# Filtering_stages.net
KiCad netlist of a schematic drawn in EAGLE
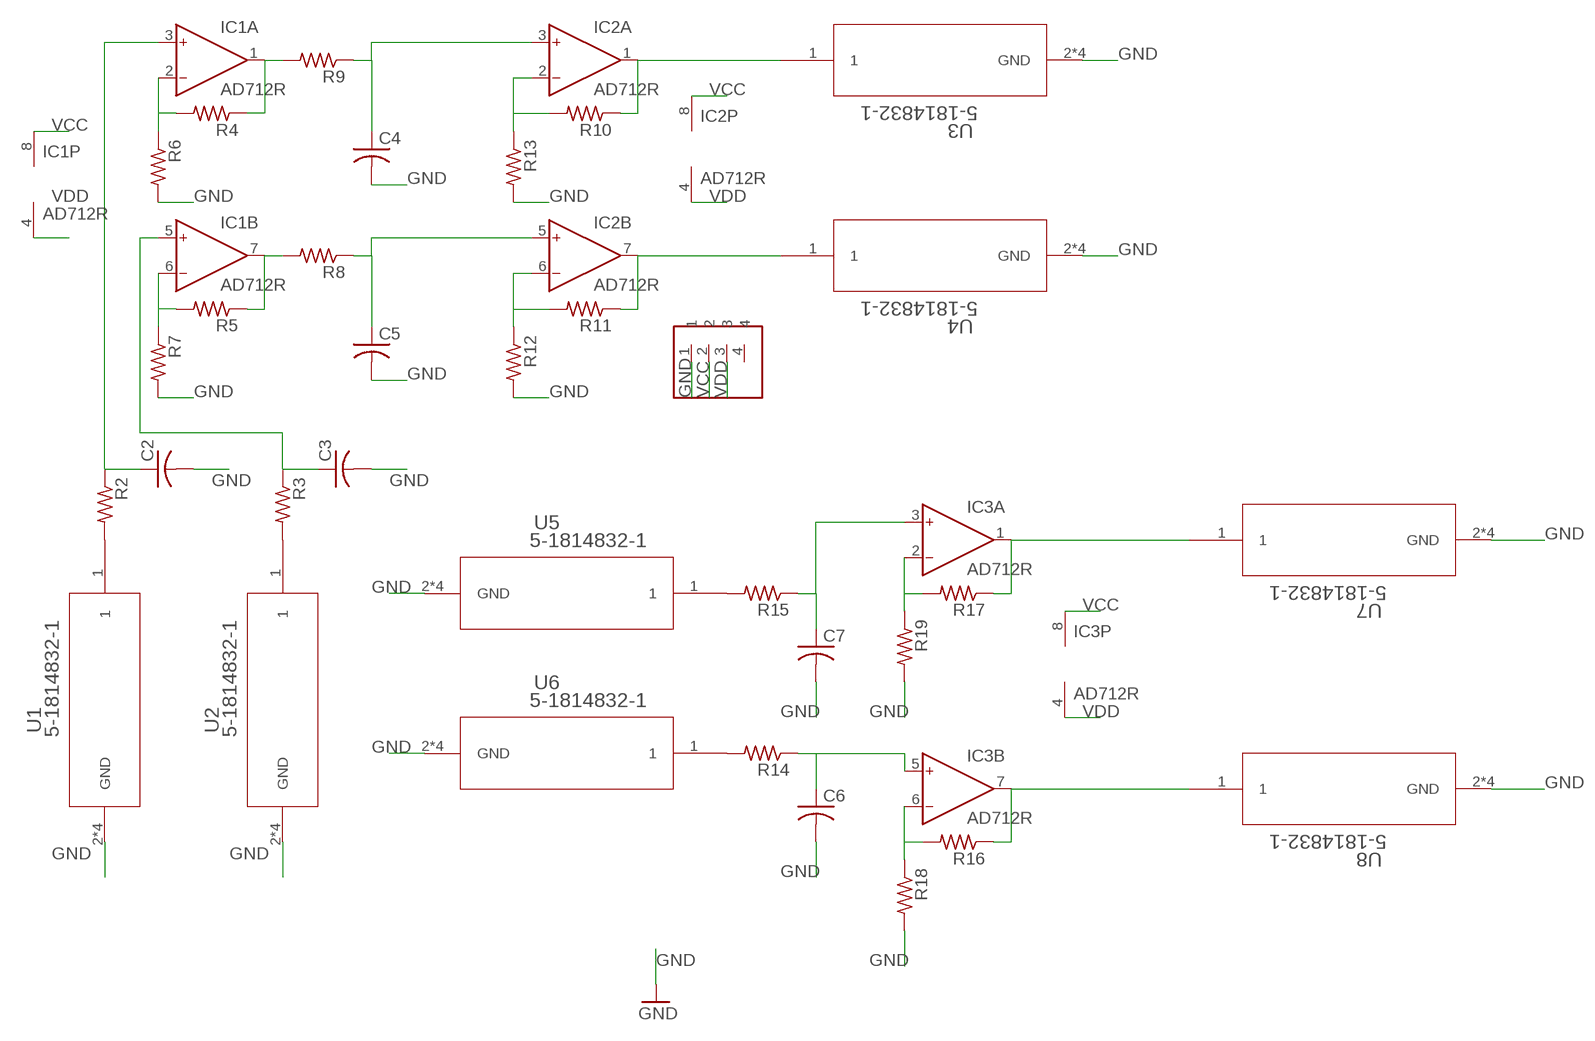
[diagram p0: schematic, sheet 1]

(export (version "E")
  (design (tool "Eeschema 10.0.6"))
  (components
    (comp (ref "C2")
      (value "C-US025-025X050")
      (footprint "eagle-import:C025-025X050")
      (libsource (lib "eagle-import") (part "C-US025-025X050"))
    )
    (comp (ref "C3")
      (value "C-US025-025X050")
      (footprint "eagle-import:C025-025X050")
      (libsource (lib "eagle-import") (part "C-US025-025X050"))
    )
    (comp (ref "C4")
      (value "C-US025-025X050")
      (footprint "eagle-import:C025-025X050")
      (libsource (lib "eagle-import") (part "C-US025-025X050"))
    )
    (comp (ref "C5")
      (value "C-US025-025X050")
      (footprint "eagle-import:C025-025X050")
      (libsource (lib "eagle-import") (part "C-US025-025X050"))
    )
    (comp (ref "C6")
      (value "C-US025-025X050")
      (footprint "eagle-import:C025-025X050")
      (libsource (lib "eagle-import") (part "C-US025-025X050"))
    )
    (comp (ref "C7")
      (value "C-US025-025X050")
      (footprint "eagle-import:C025-025X050")
      (libsource (lib "eagle-import") (part "C-US025-025X050"))
    )
    (comp (ref "IC1")
      (value "AD712R")
      (footprint "eagle-import:SO8")
      (fields (field (name "MF") "ALTERA CORPORATION") (field (name "MPN") "AD712KRZ"))
      (libsource (lib "eagle-import") (part "AD712R"))
    )
    (comp (ref "IC2")
      (value "AD712R")
      (footprint "eagle-import:SO8")
      (fields (field (name "MF") "ALTERA CORPORATION") (field (name "MPN") "AD712KRZ"))
      (libsource (lib "eagle-import") (part "AD712R"))
    )
    (comp (ref "IC3")
      (value "AD712R")
      (footprint "eagle-import:SO8")
      (fields (field (name "MF") "ALTERA CORPORATION") (field (name "MPN") "AD712KRZ"))
      (libsource (lib "eagle-import") (part "AD712R"))
    )
    (comp (ref "R2")
      (value "R-US_0204/7")
      (footprint "eagle-import:0204_7")
      (libsource (lib "eagle-import") (part "R-US_0204/7"))
    )
    (comp (ref "R3")
      (value "R-US_0204/7")
      (footprint "eagle-import:0204_7")
      (libsource (lib "eagle-import") (part "R-US_0204/7"))
    )
    (comp (ref "R4")
      (value "R-US_0204/7")
      (footprint "eagle-import:0204_7")
      (libsource (lib "eagle-import") (part "R-US_0204/7"))
    )
    (comp (ref "R5")
      (value "R-US_0204/7")
      (footprint "eagle-import:0204_7")
      (libsource (lib "eagle-import") (part "R-US_0204/7"))
    )
    (comp (ref "R6")
      (value "R-US_0204/7")
      (footprint "eagle-import:0204_7")
      (libsource (lib "eagle-import") (part "R-US_0204/7"))
    )
    (comp (ref "R7")
      (value "R-US_0204/7")
      (footprint "eagle-import:0204_7")
      (libsource (lib "eagle-import") (part "R-US_0204/7"))
    )
    (comp (ref "R8")
      (value "R-US_0204/7")
      (footprint "eagle-import:0204_7")
      (libsource (lib "eagle-import") (part "R-US_0204/7"))
    )
    (comp (ref "R9")
      (value "R-US_0204/7")
      (footprint "eagle-import:0204_7")
      (libsource (lib "eagle-import") (part "R-US_0204/7"))
    )
    (comp (ref "R10")
      (value "R-US_0204/7")
      (footprint "eagle-import:0204_7")
      (libsource (lib "eagle-import") (part "R-US_0204/7"))
    )
    (comp (ref "R11")
      (value "R-US_0204/7")
      (footprint "eagle-import:0204_7")
      (libsource (lib "eagle-import") (part "R-US_0204/7"))
    )
    (comp (ref "R12")
      (value "R-US_0204/7")
      (footprint "eagle-import:0204_7")
      (libsource (lib "eagle-import") (part "R-US_0204/7"))
    )
    (comp (ref "R13")
      (value "R-US_0204/7")
      (footprint "eagle-import:0204_7")
      (libsource (lib "eagle-import") (part "R-US_0204/7"))
    )
    (comp (ref "R14")
      (value "R-US_0204/7")
      (footprint "eagle-import:0204_7")
      (libsource (lib "eagle-import") (part "R-US_0204/7"))
    )
    (comp (ref "R15")
      (value "R-US_0204/7")
      (footprint "eagle-import:0204_7")
      (libsource (lib "eagle-import") (part "R-US_0204/7"))
    )
    (comp (ref "R16")
      (value "R-US_0204/7")
      (footprint "eagle-import:0204_7")
      (libsource (lib "eagle-import") (part "R-US_0204/7"))
    )
    (comp (ref "R17")
      (value "R-US_0204/7")
      (footprint "eagle-import:0204_7")
      (libsource (lib "eagle-import") (part "R-US_0204/7"))
    )
    (comp (ref "R18")
      (value "R-US_0204/7")
      (footprint "eagle-import:0204_7")
      (libsource (lib "eagle-import") (part "R-US_0204/7"))
    )
    (comp (ref "R19")
      (value "R-US_0204/7")
      (footprint "eagle-import:0204_7")
      (libsource (lib "eagle-import") (part "R-US_0204/7"))
    )
    (comp (ref "U$1")
      (value "ED2582-ND")
      (footprint "eagle-import:ED2582-ND")
      (libsource (lib "eagle-import") (part "ED2582-ND"))
    )
    (comp (ref "U1")
      (value "5-1814832-1")
      (footprint "eagle-import:5-1814832-1")
      (fields (field (name "COPYRIGHT") "Copyright (C) 2015 Accelerated Designs. All rights reserved"))
      (libsource (lib "eagle-import") (part "5-1814832-1"))
    )
    (comp (ref "U2")
      (value "5-1814832-1")
      (footprint "eagle-import:5-1814832-1")
      (fields (field (name "COPYRIGHT") "Copyright (C) 2015 Accelerated Designs. All rights reserved"))
      (libsource (lib "eagle-import") (part "5-1814832-1"))
    )
    (comp (ref "U3")
      (value "5-1814832-1")
      (footprint "eagle-import:5-1814832-1")
      (fields (field (name "COPYRIGHT") "Copyright (C) 2015 Accelerated Designs. All rights reserved"))
      (libsource (lib "eagle-import") (part "5-1814832-1"))
    )
    (comp (ref "U4")
      (value "5-1814832-1")
      (footprint "eagle-import:5-1814832-1")
      (fields (field (name "COPYRIGHT") "Copyright (C) 2015 Accelerated Designs. All rights reserved"))
      (libsource (lib "eagle-import") (part "5-1814832-1"))
    )
    (comp (ref "U5")
      (value "5-1814832-1")
      (footprint "eagle-import:5-1814832-1")
      (fields (field (name "COPYRIGHT") "Copyright (C) 2015 Accelerated Designs. All rights reserved"))
      (libsource (lib "eagle-import") (part "5-1814832-1"))
    )
    (comp (ref "U6")
      (value "5-1814832-1")
      (footprint "eagle-import:5-1814832-1")
      (fields (field (name "COPYRIGHT") "Copyright (C) 2015 Accelerated Designs. All rights reserved"))
      (libsource (lib "eagle-import") (part "5-1814832-1"))
    )
    (comp (ref "U7")
      (value "5-1814832-1")
      (footprint "eagle-import:5-1814832-1")
      (fields (field (name "COPYRIGHT") "Copyright (C) 2015 Accelerated Designs. All rights reserved"))
      (libsource (lib "eagle-import") (part "5-1814832-1"))
    )
    (comp (ref "U8")
      (value "5-1814832-1")
      (footprint "eagle-import:5-1814832-1")
      (fields (field (name "COPYRIGHT") "Copyright (C) 2015 Accelerated Designs. All rights reserved"))
      (libsource (lib "eagle-import") (part "5-1814832-1"))
    )
  )
  (nets
    (net (code "1") (name "/VCC") (class "Default")
      (node (ref "IC1") (pin "8") (pinfunction "V+_8") (pintype "power_in"))
      (node (ref "IC2") (pin "8") (pinfunction "V+_8") (pintype "power_in"))
      (node (ref "IC3") (pin "8") (pinfunction "V+_8") (pintype "power_in"))
      (node (ref "U$1") (pin "2") (pinfunction "2_2") (pintype "bidirectional"))
    )
    (net (code "2") (name "/VDD") (class "Default")
      (node (ref "IC1") (pin "4") (pinfunction "V-_4") (pintype "power_in"))
      (node (ref "IC2") (pin "4") (pinfunction "V-_4") (pintype "power_in"))
      (node (ref "IC3") (pin "4") (pinfunction "V-_4") (pintype "power_in"))
      (node (ref "U$1") (pin "3") (pinfunction "3_3") (pintype "bidirectional"))
    )
    (net (code "3") (name "GND") (class "Default")
      (node (ref "C2") (pin "2") (pinfunction "2_2") (pintype "passive"))
      (node (ref "C3") (pin "2") (pinfunction "2_2") (pintype "passive"))
      (node (ref "C4") (pin "2") (pinfunction "2_2") (pintype "passive"))
      (node (ref "C5") (pin "2") (pinfunction "2_2") (pintype "passive"))
      (node (ref "C6") (pin "2") (pinfunction "2_2") (pintype "passive"))
      (node (ref "C7") (pin "2") (pinfunction "2_2") (pintype "passive"))
      (node (ref "R12") (pin "2") (pinfunction "2_2") (pintype "passive"))
      (node (ref "R13") (pin "2") (pinfunction "2_2") (pintype "passive"))
      (node (ref "R18") (pin "2") (pinfunction "2_2") (pintype "passive"))
      (node (ref "R19") (pin "2") (pinfunction "2_2") (pintype "passive"))
      (node (ref "R6") (pin "2") (pinfunction "2_2") (pintype "passive"))
      (node (ref "R7") (pin "2") (pinfunction "2_2") (pintype "passive"))
      (node (ref "U$1") (pin "1") (pinfunction "1_1") (pintype "bidirectional"))
      (node (ref "U1") (pin "2") (pinfunction "GND_2") (pintype "bidirectional"))
      (node (ref "U1") (pin "3") (pinfunction "GND_3") (pintype "bidirectional"))
      (node (ref "U1") (pin "4") (pinfunction "GND_4") (pintype "bidirectional"))
      (node (ref "U1") (pin "5") (pinfunction "GND_5") (pintype "bidirectional"))
      (node (ref "U2") (pin "2") (pinfunction "GND_2") (pintype "bidirectional"))
      (node (ref "U2") (pin "3") (pinfunction "GND_3") (pintype "bidirectional"))
      (node (ref "U2") (pin "4") (pinfunction "GND_4") (pintype "bidirectional"))
      (node (ref "U2") (pin "5") (pinfunction "GND_5") (pintype "bidirectional"))
      (node (ref "U3") (pin "2") (pinfunction "GND_2") (pintype "bidirectional"))
      (node (ref "U3") (pin "3") (pinfunction "GND_3") (pintype "bidirectional"))
      (node (ref "U3") (pin "4") (pinfunction "GND_4") (pintype "bidirectional"))
      (node (ref "U3") (pin "5") (pinfunction "GND_5") (pintype "bidirectional"))
      (node (ref "U4") (pin "2") (pinfunction "GND_2") (pintype "bidirectional"))
      (node (ref "U4") (pin "3") (pinfunction "GND_3") (pintype "bidirectional"))
      (node (ref "U4") (pin "4") (pinfunction "GND_4") (pintype "bidirectional"))
      (node (ref "U4") (pin "5") (pinfunction "GND_5") (pintype "bidirectional"))
      (node (ref "U5") (pin "2") (pinfunction "GND_2") (pintype "bidirectional"))
      (node (ref "U5") (pin "3") (pinfunction "GND_3") (pintype "bidirectional"))
      (node (ref "U5") (pin "4") (pinfunction "GND_4") (pintype "bidirectional"))
      (node (ref "U5") (pin "5") (pinfunction "GND_5") (pintype "bidirectional"))
      (node (ref "U6") (pin "2") (pinfunction "GND_2") (pintype "bidirectional"))
      (node (ref "U6") (pin "3") (pinfunction "GND_3") (pintype "bidirectional"))
      (node (ref "U6") (pin "4") (pinfunction "GND_4") (pintype "bidirectional"))
      (node (ref "U6") (pin "5") (pinfunction "GND_5") (pintype "bidirectional"))
      (node (ref "U7") (pin "2") (pinfunction "GND_2") (pintype "bidirectional"))
      (node (ref "U7") (pin "3") (pinfunction "GND_3") (pintype "bidirectional"))
      (node (ref "U7") (pin "4") (pinfunction "GND_4") (pintype "bidirectional"))
      (node (ref "U7") (pin "5") (pinfunction "GND_5") (pintype "bidirectional"))
      (node (ref "U8") (pin "2") (pinfunction "GND_2") (pintype "bidirectional"))
      (node (ref "U8") (pin "3") (pinfunction "GND_3") (pintype "bidirectional"))
      (node (ref "U8") (pin "4") (pinfunction "GND_4") (pintype "bidirectional"))
      (node (ref "U8") (pin "5") (pinfunction "GND_5") (pintype "bidirectional"))
    )
    (net (code "4") (name "Net-(IC1A-IN+)") (class "Default")
      (node (ref "C2") (pin "1") (pinfunction "1_1") (pintype "passive"))
      (node (ref "IC1") (pin "3") (pinfunction "IN+_3") (pintype "input"))
      (node (ref "R2") (pin "1") (pinfunction "1_1") (pintype "passive"))
    )
    (net (code "5") (name "Net-(IC1A-IN-)") (class "Default")
      (node (ref "IC1") (pin "2") (pinfunction "IN-_2") (pintype "input"))
      (node (ref "R4") (pin "2") (pinfunction "2_2") (pintype "passive"))
      (node (ref "R6") (pin "1") (pinfunction "1_1") (pintype "passive"))
    )
    (net (code "6") (name "Net-(IC1A-OUT)") (class "Default")
      (node (ref "IC1") (pin "1") (pinfunction "OUT_1") (pintype "output"))
      (node (ref "R4") (pin "1") (pinfunction "1_1") (pintype "passive"))
      (node (ref "R9") (pin "2") (pinfunction "2_2") (pintype "passive"))
    )
    (net (code "7") (name "Net-(IC1B-IN+)") (class "Default")
      (node (ref "C3") (pin "1") (pinfunction "1_1") (pintype "passive"))
      (node (ref "IC1") (pin "5") (pinfunction "IN+_5") (pintype "input"))
      (node (ref "R3") (pin "1") (pinfunction "1_1") (pintype "passive"))
    )
    (net (code "8") (name "Net-(IC1B-IN-)") (class "Default")
      (node (ref "IC1") (pin "6") (pinfunction "IN-_6") (pintype "input"))
      (node (ref "R5") (pin "2") (pinfunction "2_2") (pintype "passive"))
      (node (ref "R7") (pin "1") (pinfunction "1_1") (pintype "passive"))
    )
    (net (code "9") (name "Net-(IC1B-OUT)") (class "Default")
      (node (ref "IC1") (pin "7") (pinfunction "OUT_7") (pintype "output"))
      (node (ref "R5") (pin "1") (pinfunction "1_1") (pintype "passive"))
      (node (ref "R8") (pin "2") (pinfunction "2_2") (pintype "passive"))
    )
    (net (code "10") (name "Net-(IC2A-IN+)") (class "Default")
      (node (ref "C4") (pin "1") (pinfunction "1_1") (pintype "passive"))
      (node (ref "IC2") (pin "3") (pinfunction "IN+_3") (pintype "input"))
      (node (ref "R9") (pin "1") (pinfunction "1_1") (pintype "passive"))
    )
    (net (code "11") (name "Net-(IC2A-IN-)") (class "Default")
      (node (ref "IC2") (pin "2") (pinfunction "IN-_2") (pintype "input"))
      (node (ref "R10") (pin "2") (pinfunction "2_2") (pintype "passive"))
      (node (ref "R13") (pin "1") (pinfunction "1_1") (pintype "passive"))
    )
    (net (code "12") (name "Net-(IC2A-OUT)") (class "Default")
      (node (ref "IC2") (pin "1") (pinfunction "OUT_1") (pintype "output"))
      (node (ref "R10") (pin "1") (pinfunction "1_1") (pintype "passive"))
      (node (ref "U3") (pin "1") (pinfunction "1_1") (pintype "passive"))
    )
    (net (code "13") (name "Net-(IC2B-IN+)") (class "Default")
      (node (ref "C5") (pin "1") (pinfunction "1_1") (pintype "passive"))
      (node (ref "IC2") (pin "5") (pinfunction "IN+_5") (pintype "input"))
      (node (ref "R8") (pin "1") (pinfunction "1_1") (pintype "passive"))
    )
    (net (code "14") (name "Net-(IC2B-IN-)") (class "Default")
      (node (ref "IC2") (pin "6") (pinfunction "IN-_6") (pintype "input"))
      (node (ref "R11") (pin "2") (pinfunction "2_2") (pintype "passive"))
      (node (ref "R12") (pin "1") (pinfunction "1_1") (pintype "passive"))
    )
    (net (code "15") (name "Net-(IC2B-OUT)") (class "Default")
      (node (ref "IC2") (pin "7") (pinfunction "OUT_7") (pintype "output"))
      (node (ref "R11") (pin "1") (pinfunction "1_1") (pintype "passive"))
      (node (ref "U4") (pin "1") (pinfunction "1_1") (pintype "passive"))
    )
    (net (code "16") (name "Net-(IC3A-IN+)") (class "Default")
      (node (ref "C7") (pin "1") (pinfunction "1_1") (pintype "passive"))
      (node (ref "IC3") (pin "3") (pinfunction "IN+_3") (pintype "input"))
      (node (ref "R15") (pin "1") (pinfunction "1_1") (pintype "passive"))
    )
    (net (code "17") (name "Net-(IC3A-IN-)") (class "Default")
      (node (ref "IC3") (pin "2") (pinfunction "IN-_2") (pintype "input"))
      (node (ref "R17") (pin "2") (pinfunction "2_2") (pintype "passive"))
      (node (ref "R19") (pin "1") (pinfunction "1_1") (pintype "passive"))
    )
    (net (code "18") (name "Net-(IC3A-OUT)") (class "Default")
      (node (ref "IC3") (pin "1") (pinfunction "OUT_1") (pintype "output"))
      (node (ref "R17") (pin "1") (pinfunction "1_1") (pintype "passive"))
      (node (ref "U7") (pin "1") (pinfunction "1_1") (pintype "passive"))
    )
    (net (code "19") (name "Net-(IC3B-IN+)") (class "Default")
      (node (ref "C6") (pin "1") (pinfunction "1_1") (pintype "passive"))
      (node (ref "IC3") (pin "5") (pinfunction "IN+_5") (pintype "input"))
      (node (ref "R14") (pin "1") (pinfunction "1_1") (pintype "passive"))
    )
    (net (code "20") (name "Net-(IC3B-IN-)") (class "Default")
      (node (ref "IC3") (pin "6") (pinfunction "IN-_6") (pintype "input"))
      (node (ref "R16") (pin "2") (pinfunction "2_2") (pintype "passive"))
      (node (ref "R18") (pin "1") (pinfunction "1_1") (pintype "passive"))
    )
    (net (code "21") (name "Net-(IC3B-OUT)") (class "Default")
      (node (ref "IC3") (pin "7") (pinfunction "OUT_7") (pintype "output"))
      (node (ref "R16") (pin "1") (pinfunction "1_1") (pintype "passive"))
      (node (ref "U8") (pin "1") (pinfunction "1_1") (pintype "passive"))
    )
    (net (code "22") (name "Net-(R2-Pad2)") (class "Default")
      (node (ref "R2") (pin "2") (pinfunction "2_2") (pintype "passive"))
      (node (ref "U1") (pin "1") (pinfunction "1_1") (pintype "passive"))
    )
    (net (code "23") (name "Net-(R3-Pad2)") (class "Default")
      (node (ref "R3") (pin "2") (pinfunction "2_2") (pintype "passive"))
      (node (ref "U2") (pin "1") (pinfunction "1_1") (pintype "passive"))
    )
    (net (code "24") (name "Net-(R14-Pad2)") (class "Default")
      (node (ref "R14") (pin "2") (pinfunction "2_2") (pintype "passive"))
      (node (ref "U6") (pin "1") (pinfunction "1_1") (pintype "passive"))
    )
    (net (code "25") (name "Net-(R15-Pad2)") (class "Default")
      (node (ref "R15") (pin "2") (pinfunction "2_2") (pintype "passive"))
      (node (ref "U5") (pin "1") (pinfunction "1_1") (pintype "passive"))
    )
    (net (code "26") (name "unconnected-(U$1-Pad4)") (class "Default")
      (node (ref "U$1") (pin "4") (pinfunction "4_4") (pintype "bidirectional"))
    )
  )
)
